# load_cell_amplifiers.net
KiCad netlist of a schematic drawn in Altium Designer
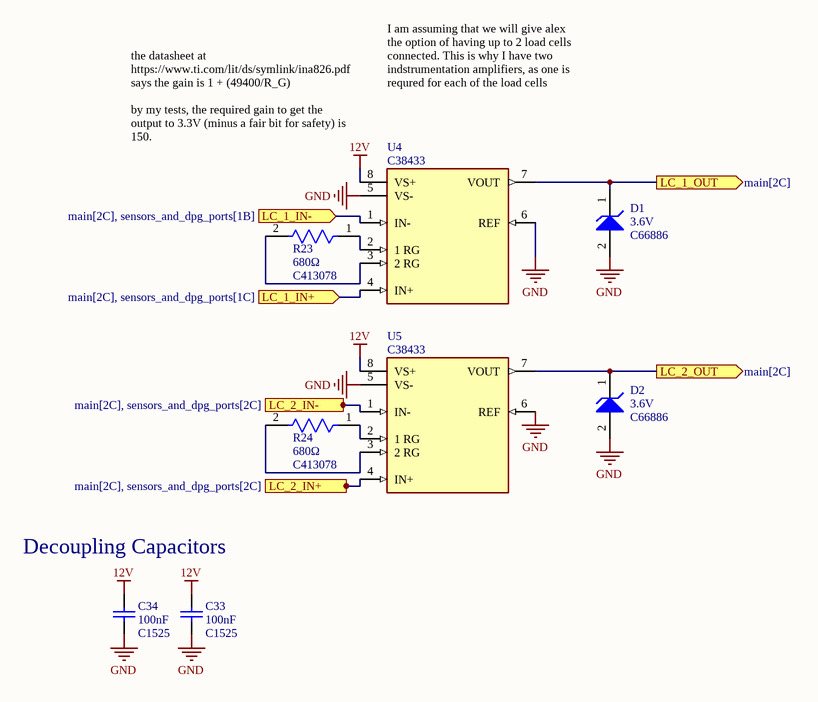
[diagram p0: load_cell_amplifiers.SchDoc]

(export (version "E")
  (design (tool "Eeschema 10.0.6"))
  (components
    (comp (ref "C33")
      (value "CL05B104KO5NNNC")
      (footprint "CAPC1050X55X23NL05T13")
      (description "Chip Capacitor, 100 nF, +/- 10%, 16 V, -55 to 125 degC, 0402 (1005 Metric), RoHS, Tape and Reel")
      (fields
        (field (name "MANUFACTURER") "Samsung Electro-Mechanics")
        (field (name "JLCPCB PART") "C1525")
        (field (name "CAPACITANCE") "100nF")
      )
      (libsource (lib "James Cook University") (part "CAP-NP-2"))
    )
    (comp (ref "C34")
      (value "CL05B104KO5NNNC")
      (footprint "CAPC1050X55X23NL05T13")
      (description "Chip Capacitor, 100 nF, +/- 10%, 16 V, -55 to 125 degC, 0402 (1005 Metric), RoHS, Tape and Reel")
      (fields
        (field (name "MANUFACTURER") "Samsung Electro-Mechanics")
        (field (name "JLCPCB PART") "C1525")
        (field (name "CAPACITANCE") "100nF")
      )
      (libsource (lib "James Cook University") (part "CAP-NP-2"))
    )
    (comp (ref "D1")
      (value "MMSZ4685T1G")
      (footprint "ONSC-SOD-123-2-425-04_V")
      (description "Zener Voltage Regulator, 500 mW, 2-Pin SOD-123, Pb-Free, Tape and Reel")
      (fields
        (field (name "MANUFACTURER") "On Semiconductor")
        (field (name "VZ TYP (V)") "3.6V")
        (field (name "JLCPCB PART") "C66886")
      )
      (libsource (lib "Altium Content Vault") (part "ONSC-K1A2-2"))
    )
    (comp (ref "D2")
      (value "MMSZ4685T1G")
      (footprint "ONSC-SOD-123-2-425-04_V")
      (description "Zener Voltage Regulator, 500 mW, 2-Pin SOD-123, Pb-Free, Tape and Reel")
      (fields
        (field (name "MANUFACTURER") "On Semiconductor")
        (field (name "VZ TYP (V)") "3.6V")
        (field (name "JLCPCB PART") "C66886")
      )
      (libsource (lib "Altium Content Vault") (part "ONSC-K1A2-2"))
    )
    (comp (ref "R23")
      (value "ERJ-2RKF6800X")
      (footprint "FP-ERJ2RK-MFG")
      (fields
        (field (name "RESISTANCE") "680Ω")
        (field (name "TOLERANCE") "1%")
        (field (name "JLCPCB PART") "C413078")
      )
      (libsource (lib "Altium Content Vault") (part "1029c3af85768c4190bb7ad29bc67b5"))
    )
    (comp (ref "R24")
      (value "ERJ-2RKF6800X")
      (footprint "FP-ERJ2RK-MFG")
      (fields
        (field (name "RESISTANCE") "680Ω")
        (field (name "TOLERANCE") "1%")
        (field (name "JLCPCB PART") "C413078")
      )
      (libsource (lib "Altium Content Vault") (part "1029c3af85768c4190bb7ad29bc67b5"))
    )
    (comp (ref "U4")
      (value "INA826AIDR")
      (footprint "FP-D0008A-IPC_A")
      (description "IC INST AMP 1 CIRCUIT 8SOIC")
      (fields (field (name "JLC PART NUMBER") "C38433") (field (name "JLCPCB PART") "C38433"))
      (libsource (lib "Altium Content Vault") (part "037b479d141f114d33bcf3e617bad63"))
    )
    (comp (ref "U5")
      (value "INA826AIDR")
      (footprint "FP-D0008A-IPC_A")
      (description "IC INST AMP 1 CIRCUIT 8SOIC")
      (fields (field (name "JLC PART NUMBER") "C38433") (field (name "JLCPCB PART") "C38433"))
      (libsource (lib "Altium Content Vault") (part "037b479d141f114d33bcf3e617bad63"))
    )
  )
  (nets
    (net (code "1") (name "/LC_1_IN+") (class "Default")
      (node (ref "U4") (pin "4") (pinfunction "IN+_4") (pintype "input"))
    )
    (net (code "2") (name "/LC_1_IN-") (class "Default")
      (node (ref "U4") (pin "1") (pinfunction "IN-_1") (pintype "input"))
    )
    (net (code "3") (name "/LC_1_OUT") (class "Default")
      (node (ref "D1") (pin "1") (pinfunction "K_1") (pintype "passive"))
      (node (ref "U4") (pin "7") (pinfunction "VOUT_7") (pintype "output"))
    )
    (net (code "4") (name "/LC_2_IN+") (class "Default")
      (node (ref "U5") (pin "4") (pinfunction "IN+_4") (pintype "input"))
    )
    (net (code "5") (name "/LC_2_IN-") (class "Default")
      (node (ref "U5") (pin "1") (pinfunction "IN-_1") (pintype "input"))
    )
    (net (code "6") (name "/LC_2_OUT") (class "Default")
      (node (ref "D2") (pin "1") (pinfunction "K_1") (pintype "passive"))
      (node (ref "U5") (pin "7") (pinfunction "VOUT_7") (pintype "output"))
    )
    (net (code "7") (name "12V") (class "Default")
      (node (ref "C33") (pin "2") (pinfunction "2_2") (pintype "passive"))
      (node (ref "C34") (pin "2") (pinfunction "2_2") (pintype "passive"))
      (node (ref "U4") (pin "8") (pinfunction "VS+_8") (pintype "power_in"))
      (node (ref "U5") (pin "8") (pinfunction "VS+_8") (pintype "power_in"))
    )
    (net (code "8") (name "GND") (class "Default")
      (node (ref "C33") (pin "1") (pinfunction "1_1") (pintype "passive"))
      (node (ref "C34") (pin "1") (pinfunction "1_1") (pintype "passive"))
      (node (ref "D1") (pin "2") (pinfunction "A_2") (pintype "passive"))
      (node (ref "D2") (pin "2") (pinfunction "A_2") (pintype "passive"))
      (node (ref "U4") (pin "5") (pinfunction "VS-_5") (pintype "power_in"))
      (node (ref "U4") (pin "6") (pinfunction "REF_6") (pintype "input"))
      (node (ref "U5") (pin "5") (pinfunction "VS-_5") (pintype "power_in"))
      (node (ref "U5") (pin "6") (pinfunction "REF_6") (pintype "input"))
    )
    (net (code "9") (name "Net-(U4-1_RG)") (class "Default")
      (node (ref "R23") (pin "1") (pinfunction "1_1") (pintype "passive"))
      (node (ref "U4") (pin "2") (pinfunction "1_RG_2") (pintype "input"))
    )
    (net (code "10") (name "Net-(U4-2_RG)") (class "Default")
      (node (ref "R23") (pin "2") (pinfunction "2_2") (pintype "passive"))
      (node (ref "U4") (pin "3") (pinfunction "2_RG_3") (pintype "input"))
    )
    (net (code "11") (name "Net-(U5-1_RG)") (class "Default")
      (node (ref "R24") (pin "1") (pinfunction "1_1") (pintype "passive"))
      (node (ref "U5") (pin "2") (pinfunction "1_RG_2") (pintype "input"))
    )
    (net (code "12") (name "Net-(U5-2_RG)") (class "Default")
      (node (ref "R24") (pin "2") (pinfunction "2_2") (pintype "passive"))
      (node (ref "U5") (pin "3") (pinfunction "2_RG_3") (pintype "input"))
    )
  )
)
